# otamatone.net
KiCad netlist of a schematic drawn in EAGLE
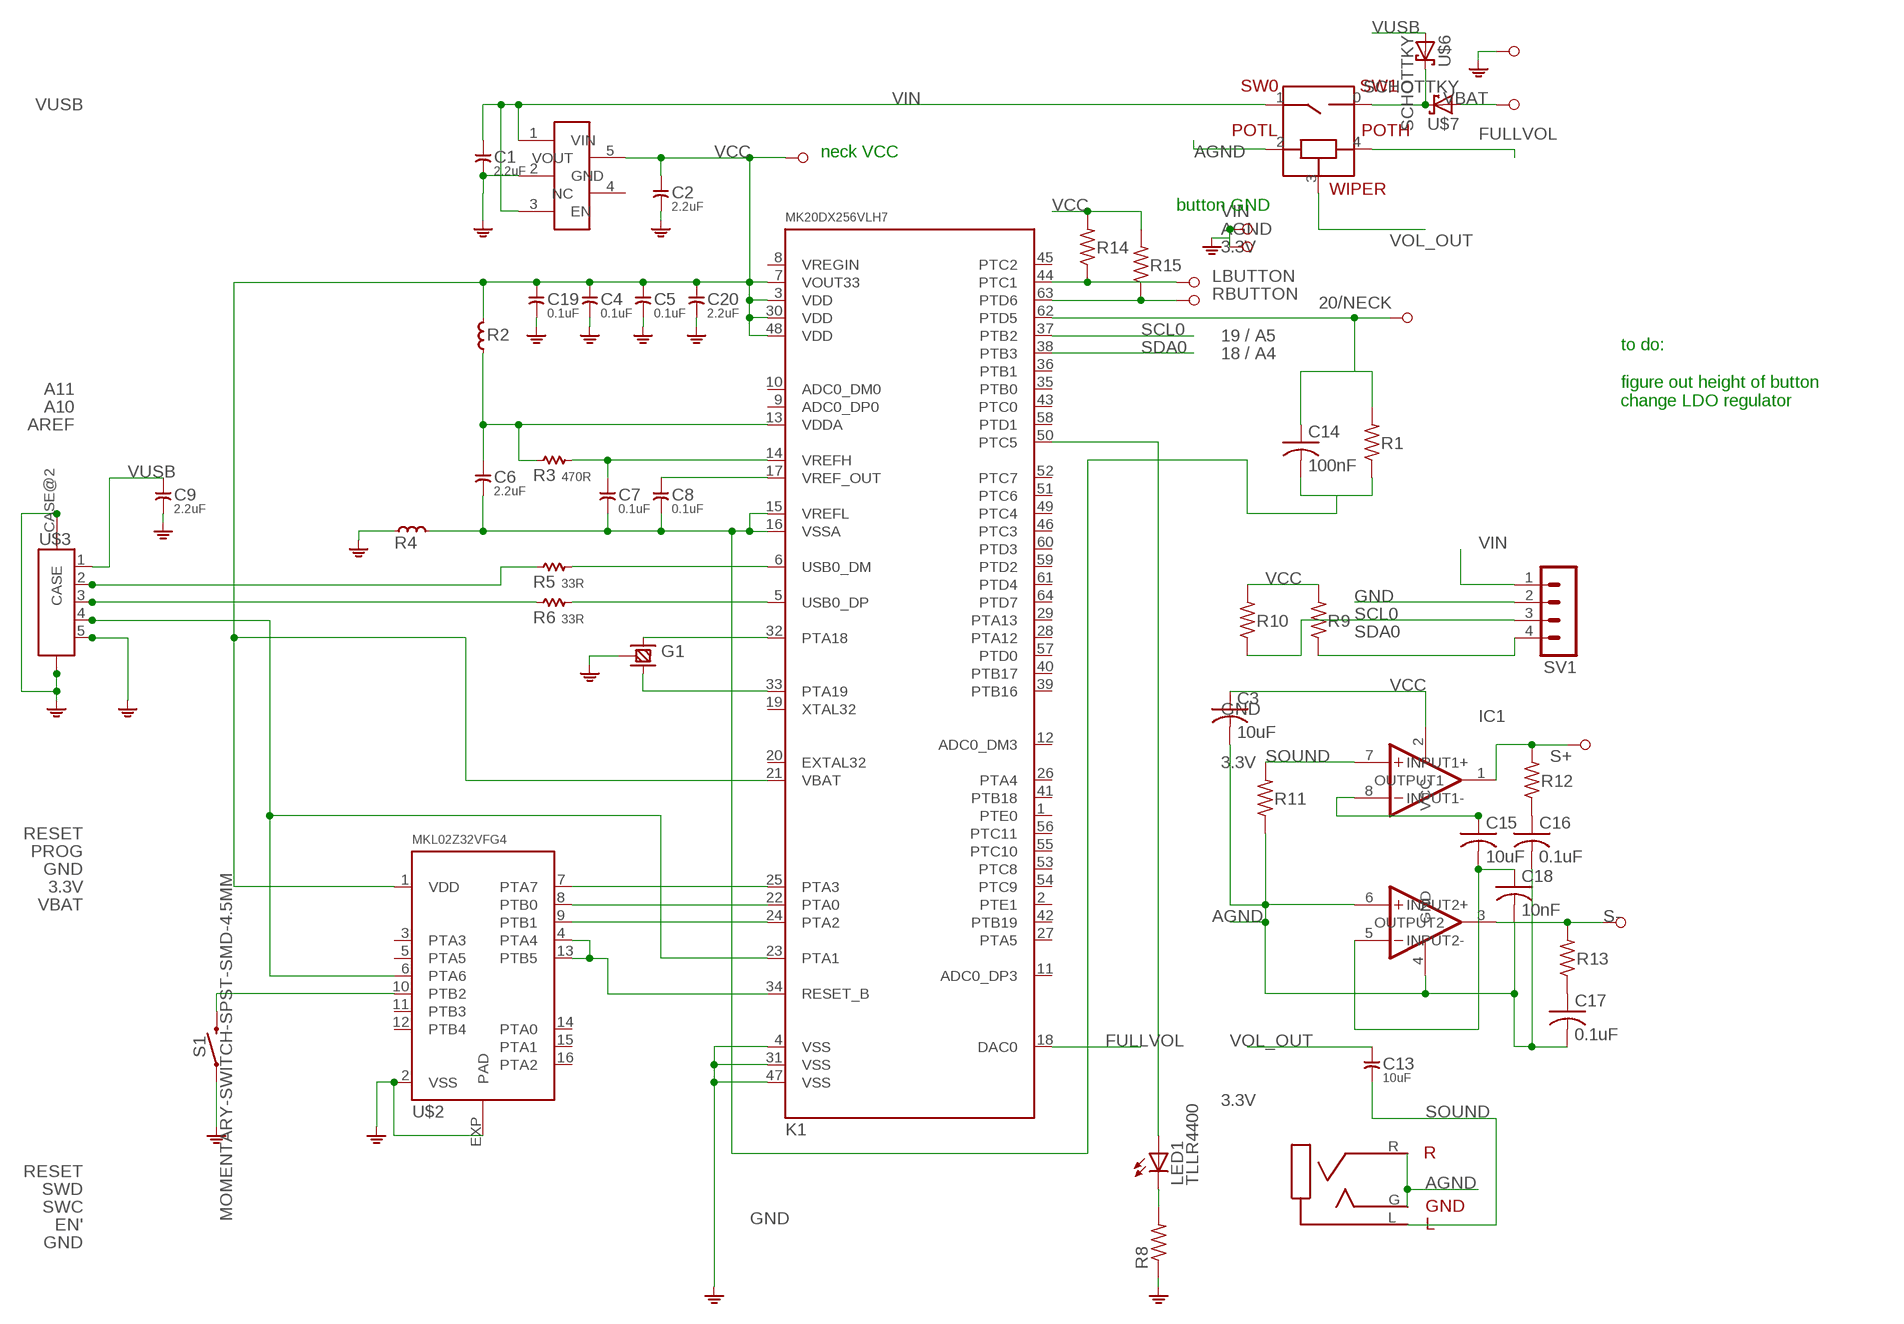
[diagram p0: schematic, sheet 1]

(export (version "E")
  (design (tool "Eeschema 10.0.6"))
  (components
    (comp (ref "B+")
      (value "PIN")
      (footprint "eagle-import:PTH_39MIL")
      (libsource (lib "eagle-import") (part "t32_ref_PIN"))
    )
    (comp (ref "B-")
      (value "PIN")
      (footprint "eagle-import:PTH_39MIL")
      (libsource (lib "eagle-import") (part "t32_ref_PIN"))
    )
    (comp (ref "C1")
      (value "2.2uF")
      (footprint "eagle-import:C0603")
      (libsource (lib "eagle-import") (part "CAPACITOR-2.2UF"))
    )
    (comp (ref "C2")
      (value "2.2uF")
      (footprint "eagle-import:C0603")
      (libsource (lib "eagle-import") (part "CAPACITOR-2.2UF"))
    )
    (comp (ref "C3")
      (value "10uF")
      (footprint "eagle-import:C0603")
      (libsource (lib "eagle-import") (part "C-USC0603"))
    )
    (comp (ref "C4")
      (value "0.1uF")
      (footprint "eagle-import:C0402")
      (libsource (lib "eagle-import") (part "CAPACITOR-0.1UF"))
    )
    (comp (ref "C5")
      (value "0.1uF")
      (footprint "eagle-import:C0402")
      (libsource (lib "eagle-import") (part "CAPACITOR-0.1UF"))
    )
    (comp (ref "C6")
      (value "2.2uF")
      (footprint "eagle-import:C0603")
      (libsource (lib "eagle-import") (part "CAPACITOR-2.2UF"))
    )
    (comp (ref "C7")
      (value "0.1uF")
      (footprint "eagle-import:C0402")
      (libsource (lib "eagle-import") (part "CAPACITOR-0.1UF"))
    )
    (comp (ref "C8")
      (value "0.1uF")
      (footprint "eagle-import:C0402")
      (libsource (lib "eagle-import") (part "CAPACITOR-0.1UF"))
    )
    (comp (ref "C9")
      (value "2.2uF")
      (footprint "eagle-import:C0603")
      (libsource (lib "eagle-import") (part "CAPACITOR-2.2UF"))
    )
    (comp (ref "C13")
      (value "10uF")
      (footprint "eagle-import:C0603")
      (fields (field (name "MF") "Vishay / Vitramon") (field (name "MPN") "VJ0603A220JXACW1BC"))
      (libsource (lib "eagle-import") (part "CAPACITOR-22PF"))
    )
    (comp (ref "C14")
      (value "100nF")
      (footprint "eagle-import:C0402")
      (libsource (lib "eagle-import") (part "C-USC0402"))
    )
    (comp (ref "C15")
      (value "10uF")
      (footprint "eagle-import:C0603")
      (libsource (lib "eagle-import") (part "C-USC0603"))
    )
    (comp (ref "C16")
      (value "0.1uF")
      (footprint "eagle-import:C0603")
      (libsource (lib "eagle-import") (part "C-USC0603"))
    )
    (comp (ref "C17")
      (value "0.1uF")
      (footprint "eagle-import:C0603")
      (libsource (lib "eagle-import") (part "C-USC0603"))
    )
    (comp (ref "C18")
      (value "10nF")
      (footprint "eagle-import:C0603")
      (libsource (lib "eagle-import") (part "C-USC0603"))
    )
    (comp (ref "C19")
      (value "0.1uF")
      (footprint "eagle-import:C0402")
      (libsource (lib "eagle-import") (part "CAPACITOR-0.1UF"))
    )
    (comp (ref "C20")
      (value "2.2uF")
      (footprint "eagle-import:C0603")
      (libsource (lib "eagle-import") (part "CAPACITOR-2.2UF"))
    )
    (comp (ref "G1")
      (value "CRYSTAL-")
      (footprint "eagle-import:CRYS")
      (libsource (lib "eagle-import") (part "CRYSTAL-"))
    )
    (comp (ref "IC1")
      (value "TDA2822MSOP8")
      (footprint "eagle-import:SOP8")
      (libsource (lib "eagle-import") (part "TDA2822MSOP8"))
    )
    (comp (ref "K1")
      (value "MK20DX256VLH7")
      (footprint "eagle-import:LQFP64-05")
      (fields (field (name "MF") "NXP"))
      (libsource (lib "eagle-import") (part "MK20DX256VLH7"))
    )
    (comp (ref "LED1")
      (value "TLLR4400")
      (footprint "eagle-import:LED3MM")
      (fields (field (name "MF") "VISHAY SEMICONDUCTOR"))
      (libsource (lib "eagle-import") (part "TLLR4400"))
    )
    (comp (ref "R1")
      (value "62K")
      (footprint "eagle-import:R0402")
      (libsource (lib "eagle-import") (part "R-US_R0402"))
    )
    (comp (ref "R2")
      (value "FERRITE")
      (footprint "eagle-import:L0603")
      (fields (field (name "MF") "Murata Electronics") (field (name "MPN") " BLM18AG601SN1D"))
      (libsource (lib "eagle-import") (part "FERRITE"))
    )
    (comp (ref "R3")
      (value "470R")
      (footprint "eagle-import:R0402")
      (libsource (lib "eagle-import") (part "RESISTOR-470R"))
    )
    (comp (ref "R4")
      (value "FERRITE")
      (footprint "eagle-import:L0603")
      (fields (field (name "MF") "Murata Electronics") (field (name "MPN") " BLM18AG601SN1D"))
      (libsource (lib "eagle-import") (part "FERRITE"))
    )
    (comp (ref "R5")
      (value "33R")
      (footprint "eagle-import:R0402")
      (libsource (lib "eagle-import") (part "RESISTOR-33R"))
    )
    (comp (ref "R6")
      (value "33R")
      (footprint "eagle-import:R0402")
      (libsource (lib "eagle-import") (part "RESISTOR-33R"))
    )
    (comp (ref "R8")
      (value "R-US_R0603")
      (footprint "eagle-import:R0603")
      (libsource (lib "eagle-import") (part "R-US_R0603"))
    )
    (comp (ref "R9")
      (value "10K")
      (footprint "eagle-import:R0402")
      (libsource (lib "eagle-import") (part "R-US_R0402"))
    )
    (comp (ref "R10")
      (value "10K")
      (footprint "eagle-import:R0402")
      (libsource (lib "eagle-import") (part "R-US_R0402"))
    )
    (comp (ref "R11")
      (value "10K")
      (footprint "eagle-import:R0603")
      (libsource (lib "eagle-import") (part "R-US_R0603"))
    )
    (comp (ref "R12")
      (value "4.7")
      (footprint "eagle-import:R0603")
      (libsource (lib "eagle-import") (part "R-US_R0603"))
    )
    (comp (ref "R13")
      (value "4.7")
      (footprint "eagle-import:R0603")
      (libsource (lib "eagle-import") (part "R-US_R0603"))
    )
    (comp (ref "R14")
      (value "10K")
      (footprint "eagle-import:R0402")
      (libsource (lib "eagle-import") (part "R-US_R0402"))
    )
    (comp (ref "R15")
      (value "10K")
      (footprint "eagle-import:R0402")
      (libsource (lib "eagle-import") (part "R-US_R0402"))
    )
    (comp (ref "S+")
      (value "PINSMT")
      (footprint "eagle-import:SMD")
      (libsource (lib "eagle-import") (part "PINSMT"))
    )
    (comp (ref "S-")
      (value "PINSMT")
      (footprint "eagle-import:SMD")
      (libsource (lib "eagle-import") (part "PINSMT"))
    )
    (comp (ref "S1")
      (value "MOMENTARY-SWITCH-SPST-SMD-4.5MM")
      (footprint "eagle-import:TACTILE_SWITCH_SMD_4.5MM")
      (libsource (lib "eagle-import") (part "MOMENTARY-SWITCH-SPST-SMD-4.5MM"))
    )
    (comp (ref "SV1")
      (value "MA04-1")
      (footprint "eagle-import:MA04-1")
      (libsource (lib "eagle-import") (part "MA04-1"))
    )
    (comp (ref "SX1")
      (value "PIN")
      (footprint "eagle-import:PTH_39MIL")
      (libsource (lib "eagle-import") (part "PIN"))
    )
    (comp (ref "SX2")
      (value "PIN")
      (footprint "eagle-import:PTH_39MIL")
      (libsource (lib "eagle-import") (part "PIN"))
    )
    (comp (ref "SX3")
      (value "PIN")
      (footprint "eagle-import:PTH_39MIL")
      (libsource (lib "eagle-import") (part "PIN"))
    )
    (comp (ref "SX4")
      (value "PIN")
      (footprint "eagle-import:PTH_39MIL")
      (libsource (lib "eagle-import") (part "PIN"))
    )
    (comp (ref "U$1")
      (value "P170S")
      (footprint "eagle-import:5PIN_POT")
      (libsource (lib "eagle-import") (part "P170S"))
    )
    (comp (ref "U$2")
      (value "MKL02Z32VFG4")
      (footprint "eagle-import:QFN16")
      (libsource (lib "eagle-import") (part "MKL02Z32VFG4"))
    )
    (comp (ref "U$3")
      (value "VERT_USB")
      (footprint "eagle-import:TALL_BOI")
      (libsource (lib "eagle-import") (part "VERT_USB"))
    )
    (comp (ref "U$4")
      (value "VERT_JACK")
      (footprint "eagle-import:AUDIOJACK")
      (libsource (lib "eagle-import") (part "VERT_JACK"))
    )
    (comp (ref "U$5")
      (value "AP2112K")
      (footprint "eagle-import:SOT25")
      (libsource (lib "eagle-import") (part "AP2112K"))
    )
    (comp (ref "U$6")
      (value "SCHOTTKY")
      (footprint "eagle-import:LED-0805")
      (libsource (lib "eagle-import") (part "SCHOTTKY"))
    )
    (comp (ref "U$7")
      (value "SCHOTTKY")
      (footprint "eagle-import:LED-0805")
      (libsource (lib "eagle-import") (part "SCHOTTKY"))
    )
    (comp (ref "Z+")
      (value "PINSMT")
      (footprint "eagle-import:SMD")
      (libsource (lib "eagle-import") (part "PINSMT"))
    )
    (comp (ref "Z-")
      (value "PINSMT")
      (footprint "eagle-import:SMD")
      (libsource (lib "eagle-import") (part "PINSMT"))
    )
  )
  (nets
    (net (code "1") (name "/20{slash}NECK") (class "Default")
      (node (ref "C14") (pin "1") (pinfunction "1_1") (pintype "passive"))
      (node (ref "K1") (pin "62") (pinfunction "PTD5_62") (pintype "bidirectional"))
      (node (ref "R1") (pin "2") (pinfunction "2_2") (pintype "passive"))
      (node (ref "Z-") (pin "P$1") (pinfunction "P$1_P$1") (pintype "bidirectional"))
    )
    (net (code "2") (name "/AGND") (class "Default")
      (node (ref "C14") (pin "2") (pinfunction "2_2") (pintype "passive"))
      (node (ref "C16") (pin "2") (pinfunction "2_2") (pintype "passive"))
      (node (ref "C17") (pin "2") (pinfunction "2_2") (pintype "passive"))
      (node (ref "C18") (pin "2") (pinfunction "2_2") (pintype "passive"))
      (node (ref "C3") (pin "2") (pinfunction "2_2") (pintype "passive"))
      (node (ref "C6") (pin "2") (pinfunction "2_2") (pintype "passive"))
      (node (ref "C7") (pin "2") (pinfunction "2_2") (pintype "passive"))
      (node (ref "C8") (pin "2") (pinfunction "2_2") (pintype "passive"))
      (node (ref "IC1") (pin "4") (pinfunction "GND_4") (pintype "bidirectional"))
      (node (ref "IC1") (pin "6") (pinfunction "INPUT2+_6") (pintype "bidirectional"))
      (node (ref "K1") (pin "15") (pinfunction "VREFL_15") (pintype "bidirectional"))
      (node (ref "K1") (pin "16") (pinfunction "VSSA_16") (pintype "bidirectional"))
      (node (ref "R1") (pin "1") (pinfunction "1_1") (pintype "passive"))
      (node (ref "R11") (pin "1") (pinfunction "1_1") (pintype "passive"))
      (node (ref "R4") (pin "2") (pinfunction "2_2") (pintype "passive"))
      (node (ref "U$1") (pin "2") (pinfunction "POTL_2") (pintype "bidirectional"))
      (node (ref "U$4") (pin "G") (pinfunction "GND_G") (pintype "bidirectional"))
      (node (ref "U$4") (pin "R") (pinfunction "R_R") (pintype "bidirectional"))
    )
    (net (code "3") (name "/FULLVOL") (class "Default")
      (node (ref "K1") (pin "18") (pinfunction "DAC0_18") (pintype "bidirectional"))
      (node (ref "U$1") (pin "4") (pinfunction "POTH_4") (pintype "bidirectional"))
    )
    (net (code "4") (name "/LBUTTON") (class "Default")
      (node (ref "K1") (pin "44") (pinfunction "PTC1_44") (pintype "bidirectional"))
      (node (ref "R14") (pin "1") (pinfunction "1_1") (pintype "passive"))
      (node (ref "SX2") (pin "1") (pinfunction "P$1_1") (pintype "bidirectional"))
    )
    (net (code "5") (name "/RBUTTON") (class "Default")
      (node (ref "K1") (pin "63") (pinfunction "PTD6_63") (pintype "bidirectional"))
      (node (ref "R15") (pin "1") (pinfunction "1_1") (pintype "passive"))
      (node (ref "SX4") (pin "1") (pinfunction "P$1_1") (pintype "bidirectional"))
    )
    (net (code "6") (name "/S+") (class "Default")
      (node (ref "IC1") (pin "1") (pinfunction "OUTPUT1_1") (pintype "bidirectional"))
      (node (ref "R12") (pin "2") (pinfunction "2_2") (pintype "passive"))
      (node (ref "S+") (pin "P$1") (pinfunction "P$1_P$1") (pintype "bidirectional"))
    )
    (net (code "7") (name "/S-") (class "Default")
      (node (ref "IC1") (pin "3") (pinfunction "OUTPUT2_3") (pintype "bidirectional"))
      (node (ref "R13") (pin "2") (pinfunction "2_2") (pintype "passive"))
      (node (ref "S-") (pin "P$1") (pinfunction "P$1_P$1") (pintype "bidirectional"))
    )
    (net (code "8") (name "/SCL0") (class "Default")
      (node (ref "K1") (pin "37") (pinfunction "PTB2_37") (pintype "bidirectional"))
      (node (ref "R10") (pin "1") (pinfunction "1_1") (pintype "passive"))
      (node (ref "SV1") (pin "3") (pinfunction "3_3") (pintype "passive"))
    )
    (net (code "9") (name "/SDA0") (class "Default")
      (node (ref "K1") (pin "38") (pinfunction "PTB3_38") (pintype "bidirectional"))
      (node (ref "R9") (pin "1") (pinfunction "1_1") (pintype "passive"))
      (node (ref "SV1") (pin "4") (pinfunction "4_4") (pintype "passive"))
    )
    (net (code "10") (name "/SOUND") (class "Default")
      (node (ref "C13") (pin "2") (pinfunction "2_2") (pintype "passive"))
      (node (ref "IC1") (pin "7") (pinfunction "INPUT1+_7") (pintype "bidirectional"))
      (node (ref "R11") (pin "2") (pinfunction "2_2") (pintype "passive"))
      (node (ref "U$4") (pin "L") (pinfunction "L_L") (pintype "bidirectional"))
    )
    (net (code "11") (name "/VBAT") (class "Default")
      (node (ref "B+") (pin "1") (pinfunction "P$1_1") (pintype "bidirectional"))
      (node (ref "U$7") (pin "+") (pinfunction "A_+") (pintype "passive"))
    )
    (net (code "12") (name "/VCC") (class "Default")
      (node (ref "C19") (pin "1") (pinfunction "1_1") (pintype "passive"))
      (node (ref "C2") (pin "1") (pinfunction "1_1") (pintype "passive"))
      (node (ref "C20") (pin "1") (pinfunction "1_1") (pintype "passive"))
      (node (ref "C3") (pin "1") (pinfunction "1_1") (pintype "passive"))
      (node (ref "C4") (pin "1") (pinfunction "1_1") (pintype "passive"))
      (node (ref "C5") (pin "1") (pinfunction "1_1") (pintype "passive"))
      (node (ref "IC1") (pin "2") (pinfunction "VCC_2") (pintype "bidirectional"))
      (node (ref "K1") (pin "21") (pinfunction "VBAT_21") (pintype "bidirectional"))
      (node (ref "K1") (pin "3") (pinfunction "VDD_3") (pintype "bidirectional"))
      (node (ref "K1") (pin "30") (pinfunction "VDD_30") (pintype "bidirectional"))
      (node (ref "K1") (pin "48") (pinfunction "VDD_48") (pintype "bidirectional"))
      (node (ref "K1") (pin "7") (pinfunction "VOUT33_7") (pintype "bidirectional"))
      (node (ref "R10") (pin "2") (pinfunction "2_2") (pintype "passive"))
      (node (ref "R14") (pin "2") (pinfunction "2_2") (pintype "passive"))
      (node (ref "R15") (pin "2") (pinfunction "2_2") (pintype "passive"))
      (node (ref "R2") (pin "2") (pinfunction "2_2") (pintype "passive"))
      (node (ref "R9") (pin "2") (pinfunction "2_2") (pintype "passive"))
      (node (ref "U$2") (pin "1") (pinfunction "VDD_1") (pintype "bidirectional"))
      (node (ref "U$5") (pin "5") (pinfunction "VOUT_5") (pintype "bidirectional"))
      (node (ref "Z+") (pin "P$1") (pinfunction "P$1_P$1") (pintype "bidirectional"))
    )
    (net (code "13") (name "/VIN") (class "Default")
      (node (ref "C1") (pin "1") (pinfunction "1_1") (pintype "passive"))
      (node (ref "SV1") (pin "1") (pinfunction "1_1") (pintype "passive"))
      (node (ref "U$1") (pin "1") (pinfunction "SW0_1") (pintype "bidirectional"))
      (node (ref "U$5") (pin "1") (pinfunction "VIN_1") (pintype "bidirectional"))
      (node (ref "U$5") (pin "3") (pinfunction "EN_3") (pintype "bidirectional"))
    )
    (net (code "14") (name "/VOL_OUT") (class "Default")
      (node (ref "C13") (pin "1") (pinfunction "1_1") (pintype "passive"))
      (node (ref "U$1") (pin "3") (pinfunction "WIPER_3") (pintype "bidirectional"))
    )
    (net (code "15") (name "/VUSB") (class "Default")
      (node (ref "C9") (pin "1") (pinfunction "1_1") (pintype "passive"))
      (node (ref "U$3") (pin "1") (pinfunction "1_1") (pintype "input"))
      (node (ref "U$6") (pin "+") (pinfunction "A_+") (pintype "passive"))
    )
    (net (code "16") (name "GND") (class "Default")
      (node (ref "B-") (pin "1") (pinfunction "P$1_1") (pintype "bidirectional"))
      (node (ref "C1") (pin "2") (pinfunction "2_2") (pintype "passive"))
      (node (ref "C19") (pin "2") (pinfunction "2_2") (pintype "passive"))
      (node (ref "C2") (pin "2") (pinfunction "2_2") (pintype "passive"))
      (node (ref "C20") (pin "2") (pinfunction "2_2") (pintype "passive"))
      (node (ref "C4") (pin "2") (pinfunction "2_2") (pintype "passive"))
      (node (ref "C5") (pin "2") (pinfunction "2_2") (pintype "passive"))
      (node (ref "C9") (pin "2") (pinfunction "2_2") (pintype "passive"))
      (node (ref "G1") (pin "P$1") (pinfunction "GND_P$1") (pintype "bidirectional"))
      (node (ref "G1") (pin "P$4") (pinfunction "GND_P$4") (pintype "bidirectional"))
      (node (ref "K1") (pin "31") (pinfunction "VSS_31") (pintype "bidirectional"))
      (node (ref "K1") (pin "4") (pinfunction "VSS_4") (pintype "bidirectional"))
      (node (ref "K1") (pin "47") (pinfunction "VSS_47") (pintype "bidirectional"))
      (node (ref "R4") (pin "1") (pinfunction "1_1") (pintype "passive"))
      (node (ref "R8") (pin "1") (pinfunction "1_1") (pintype "passive"))
      (node (ref "S1") (pin "2") (pinfunction "1_2") (pintype "passive"))
      (node (ref "S1") (pin "3") (pinfunction "1_3") (pintype "passive"))
      (node (ref "SV1") (pin "2") (pinfunction "2_2") (pintype "passive"))
      (node (ref "SX1") (pin "1") (pinfunction "P$1_1") (pintype "bidirectional"))
      (node (ref "SX3") (pin "1") (pinfunction "P$1_1") (pintype "bidirectional"))
      (node (ref "U$2") (pin "2") (pinfunction "VSS_2") (pintype "bidirectional"))
      (node (ref "U$2") (pin "EXP") (pinfunction "PAD_EXP") (pintype "bidirectional"))
      (node (ref "U$3") (pin "5") (pinfunction "5_5") (pintype "input"))
      (node (ref "U$3") (pin "CASE") (pinfunction "CASE_CASE") (pintype "input"))
      (node (ref "U$3") (pin "CASE@2") (pinfunction "CASE_CASE@2") (pintype "bidirectional"))
      (node (ref "U$5") (pin "2") (pinfunction "GND_2") (pintype "bidirectional"))
    )
    (net (code "17") (name "Net-(C16-Pad1)") (class "Default")
      (node (ref "C16") (pin "1") (pinfunction "1_1") (pintype "passive"))
      (node (ref "R12") (pin "1") (pinfunction "1_1") (pintype "passive"))
    )
    (net (code "18") (name "Net-(C17-Pad1)") (class "Default")
      (node (ref "C17") (pin "1") (pinfunction "1_1") (pintype "passive"))
      (node (ref "R13") (pin "1") (pinfunction "1_1") (pintype "passive"))
    )
    (net (code "19") (name "Net-(G1-1)") (class "Default")
      (node (ref "G1") (pin "P$2") (pinfunction "1_P$2") (pintype "passive"))
      (node (ref "K1") (pin "32") (pinfunction "PTA18_32") (pintype "bidirectional"))
    )
    (net (code "20") (name "Net-(G1-2)") (class "Default")
      (node (ref "G1") (pin "P$3") (pinfunction "2_P$3") (pintype "passive"))
      (node (ref "K1") (pin "33") (pinfunction "PTA19_33") (pintype "bidirectional"))
    )
    (net (code "21") (name "Net-(IC1-INPUT1-)") (class "Default")
      (node (ref "C15") (pin "1") (pinfunction "1_1") (pintype "passive"))
      (node (ref "IC1") (pin "8") (pinfunction "INPUT1-_8") (pintype "bidirectional"))
    )
    (net (code "22") (name "Net-(IC1-INPUT2-)") (class "Default")
      (node (ref "C15") (pin "2") (pinfunction "2_2") (pintype "passive"))
      (node (ref "C18") (pin "1") (pinfunction "1_1") (pintype "passive"))
      (node (ref "IC1") (pin "5") (pinfunction "INPUT2-_5") (pintype "bidirectional"))
    )
    (net (code "23") (name "Net-(K1-PTA0)") (class "Default")
      (node (ref "K1") (pin "22") (pinfunction "PTA0_22") (pintype "bidirectional"))
      (node (ref "U$2") (pin "8") (pinfunction "PTB0_8") (pintype "bidirectional"))
    )
    (net (code "24") (name "Net-(K1-PTA1)") (class "Default")
      (node (ref "K1") (pin "23") (pinfunction "PTA1_23") (pintype "bidirectional"))
      (node (ref "U$2") (pin "6") (pinfunction "PTA6_6") (pintype "bidirectional"))
      (node (ref "U$3") (pin "4") (pinfunction "4_4") (pintype "input"))
    )
    (net (code "25") (name "Net-(K1-PTA2)") (class "Default")
      (node (ref "K1") (pin "24") (pinfunction "PTA2_24") (pintype "bidirectional"))
      (node (ref "U$2") (pin "9") (pinfunction "PTB1_9") (pintype "bidirectional"))
    )
    (net (code "26") (name "Net-(K1-PTA3)") (class "Default")
      (node (ref "K1") (pin "25") (pinfunction "PTA3_25") (pintype "bidirectional"))
      (node (ref "U$2") (pin "7") (pinfunction "PTA7_7") (pintype "bidirectional"))
    )
    (net (code "27") (name "Net-(K1-PTC5)") (class "Default")
      (node (ref "K1") (pin "50") (pinfunction "PTC5_50") (pintype "bidirectional"))
      (node (ref "LED1") (pin "A") (pinfunction "A_A") (pintype "passive"))
    )
    (net (code "28") (name "Net-(K1-RESET_B)") (class "Default")
      (node (ref "K1") (pin "34") (pinfunction "RESET_B_34") (pintype "bidirectional"))
      (node (ref "U$2") (pin "13") (pinfunction "PTB5_13") (pintype "bidirectional"))
      (node (ref "U$2") (pin "4") (pinfunction "PTA4_4") (pintype "bidirectional"))
    )
    (net (code "29") (name "Net-(K1-USB0_DM)") (class "Default")
      (node (ref "K1") (pin "6") (pinfunction "USB0_DM_6") (pintype "bidirectional"))
      (node (ref "R5") (pin "2") (pinfunction "2_2") (pintype "passive"))
    )
    (net (code "30") (name "Net-(K1-USB0_DP)") (class "Default")
      (node (ref "K1") (pin "5") (pinfunction "USB0_DP_5") (pintype "bidirectional"))
      (node (ref "R6") (pin "2") (pinfunction "2_2") (pintype "passive"))
    )
    (net (code "31") (name "Net-(K1-VDDA)") (class "Default")
      (node (ref "C6") (pin "1") (pinfunction "1_1") (pintype "passive"))
      (node (ref "K1") (pin "13") (pinfunction "VDDA_13") (pintype "bidirectional"))
      (node (ref "R2") (pin "1") (pinfunction "1_1") (pintype "passive"))
      (node (ref "R3") (pin "1") (pinfunction "1_1") (pintype "passive"))
    )
    (net (code "32") (name "Net-(K1-VREFH)") (class "Default")
      (node (ref "C7") (pin "1") (pinfunction "1_1") (pintype "passive"))
      (node (ref "K1") (pin "14") (pinfunction "VREFH_14") (pintype "bidirectional"))
      (node (ref "R3") (pin "2") (pinfunction "2_2") (pintype "passive"))
    )
    (net (code "33") (name "Net-(K1-VREF_OUT)") (class "Default")
      (node (ref "C8") (pin "1") (pinfunction "1_1") (pintype "passive"))
      (node (ref "K1") (pin "17") (pinfunction "VREF_OUT_17") (pintype "bidirectional"))
    )
    (net (code "34") (name "Net-(LED1-C)") (class "Default")
      (node (ref "LED1") (pin "K") (pinfunction "C_K") (pintype "passive"))
      (node (ref "R8") (pin "2") (pinfunction "2_2") (pintype "passive"))
    )
    (net (code "35") (name "Net-(R5-Pad1)") (class "Default")
      (node (ref "R5") (pin "1") (pinfunction "1_1") (pintype "passive"))
      (node (ref "U$3") (pin "2") (pinfunction "2_2") (pintype "input"))
    )
    (net (code "36") (name "Net-(R6-Pad1)") (class "Default")
      (node (ref "R6") (pin "1") (pinfunction "1_1") (pintype "passive"))
      (node (ref "U$3") (pin "3") (pinfunction "3_3") (pintype "input"))
    )
    (net (code "37") (name "Net-(U$1-SW1)") (class "Default")
      (node (ref "U$1") (pin "0") (pinfunction "SW1_0") (pintype "bidirectional"))
      (node (ref "U$6") (pin "-") (pinfunction "C_-") (pintype "passive"))
      (node (ref "U$7") (pin "-") (pinfunction "C_-") (pintype "passive"))
    )
    (net (code "38") (name "Net-(U$2-PTB2)") (class "Default")
      (node (ref "S1") (pin "1") (pinfunction "2_1") (pintype "passive"))
      (node (ref "S1") (pin "4") (pinfunction "2_4") (pintype "passive"))
      (node (ref "U$2") (pin "10") (pinfunction "PTB2_10") (pintype "bidirectional"))
    )
    (net (code "39") (name "unconnected-(K1-ADC0_DM0-Pad10)") (class "Default")
      (node (ref "K1") (pin "10") (pinfunction "ADC0_DM0_10") (pintype "bidirectional"))
    )
    (net (code "40") (name "unconnected-(K1-ADC0_DM3-Pad12)") (class "Default")
      (node (ref "K1") (pin "12") (pinfunction "ADC0_DM3_12") (pintype "bidirectional"))
    )
    (net (code "41") (name "unconnected-(K1-ADC0_DP0-Pad9)") (class "Default")
      (node (ref "K1") (pin "9") (pinfunction "ADC0_DP0_9") (pintype "bidirectional"))
    )
    (net (code "42") (name "unconnected-(K1-ADC0_DP3-Pad11)") (class "Default")
      (node (ref "K1") (pin "11") (pinfunction "ADC0_DP3_11") (pintype "bidirectional"))
    )
    (net (code "43") (name "unconnected-(K1-EXTAL32-Pad20)") (class "Default")
      (node (ref "K1") (pin "20") (pinfunction "EXTAL32_20") (pintype "bidirectional"))
    )
    (net (code "44") (name "unconnected-(K1-PTA4-Pad26)") (class "Default")
      (node (ref "K1") (pin "26") (pinfunction "PTA4_26") (pintype "bidirectional"))
    )
    (net (code "45") (name "unconnected-(K1-PTA5-Pad27)") (class "Default")
      (node (ref "K1") (pin "27") (pinfunction "PTA5_27") (pintype "bidirectional"))
    )
    (net (code "46") (name "unconnected-(K1-PTA12-Pad28)") (class "Default")
      (node (ref "K1") (pin "28") (pinfunction "PTA12_28") (pintype "bidirectional"))
    )
    (net (code "47") (name "unconnected-(K1-PTA13-Pad29)") (class "Default")
      (node (ref "K1") (pin "29") (pinfunction "PTA13_29") (pintype "bidirectional"))
    )
    (net (code "48") (name "unconnected-(K1-PTB0-Pad35)") (class "Default")
      (node (ref "K1") (pin "35") (pinfunction "PTB0_35") (pintype "bidirectional"))
    )
    (net (code "49") (name "unconnected-(K1-PTB1-Pad36)") (class "Default")
      (node (ref "K1") (pin "36") (pinfunction "PTB1_36") (pintype "bidirectional"))
    )
    (net (code "50") (name "unconnected-(K1-PTB16-Pad39)") (class "Default")
      (node (ref "K1") (pin "39") (pinfunction "PTB16_39") (pintype "bidirectional"))
    )
    (net (code "51") (name "unconnected-(K1-PTB17-Pad40)") (class "Default")
      (node (ref "K1") (pin "40") (pinfunction "PTB17_40") (pintype "bidirectional"))
    )
    (net (code "52") (name "unconnected-(K1-PTB18-Pad41)") (class "Default")
      (node (ref "K1") (pin "41") (pinfunction "PTB18_41") (pintype "bidirectional"))
    )
    (net (code "53") (name "unconnected-(K1-PTB19-Pad42)") (class "Default")
      (node (ref "K1") (pin "42") (pinfunction "PTB19_42") (pintype "bidirectional"))
    )
    (net (code "54") (name "unconnected-(K1-PTC0-Pad43)") (class "Default")
      (node (ref "K1") (pin "43") (pinfunction "PTC0_43") (pintype "bidirectional"))
    )
    (net (code "55") (name "unconnected-(K1-PTC2-Pad45)") (class "Default")
      (node (ref "K1") (pin "45") (pinfunction "PTC2_45") (pintype "bidirectional"))
    )
    (net (code "56") (name "unconnected-(K1-PTC3-Pad46)") (class "Default")
      (node (ref "K1") (pin "46") (pinfunction "PTC3_46") (pintype "bidirectional"))
    )
    (net (code "57") (name "unconnected-(K1-PTC4-Pad49)") (class "Default")
      (node (ref "K1") (pin "49") (pinfunction "PTC4_49") (pintype "bidirectional"))
    )
    (net (code "58") (name "unconnected-(K1-PTC6-Pad51)") (class "Default")
      (node (ref "K1") (pin "51") (pinfunction "PTC6_51") (pintype "bidirectional"))
    )
    (net (code "59") (name "unconnected-(K1-PTC7-Pad52)") (class "Default")
      (node (ref "K1") (pin "52") (pinfunction "PTC7_52") (pintype "bidirectional"))
    )
    (net (code "60") (name "unconnected-(K1-PTC8-Pad53)") (class "Default")
      (node (ref "K1") (pin "53") (pinfunction "PTC8_53") (pintype "bidirectional"))
    )
    (net (code "61") (name "unconnected-(K1-PTC9-Pad54)") (class "Default")
      (node (ref "K1") (pin "54") (pinfunction "PTC9_54") (pintype "bidirectional"))
    )
    (net (code "62") (name "unconnected-(K1-PTC10-Pad55)") (class "Default")
      (node (ref "K1") (pin "55") (pinfunction "PTC10_55") (pintype "bidirectional"))
    )
    (net (code "63") (name "unconnected-(K1-PTC11-Pad56)") (class "Default")
      (node (ref "K1") (pin "56") (pinfunction "PTC11_56") (pintype "bidirectional"))
    )
    (net (code "64") (name "unconnected-(K1-PTD0-Pad57)") (class "Default")
      (node (ref "K1") (pin "57") (pinfunction "PTD0_57") (pintype "bidirectional"))
    )
    (net (code "65") (name "unconnected-(K1-PTD1-Pad58)") (class "Default")
      (node (ref "K1") (pin "58") (pinfunction "PTD1_58") (pintype "bidirectional"))
    )
    (net (code "66") (name "unconnected-(K1-PTD2-Pad59)") (class "Default")
      (node (ref "K1") (pin "59") (pinfunction "PTD2_59") (pintype "bidirectional"))
    )
    (net (code "67") (name "unconnected-(K1-PTD3-Pad60)") (class "Default")
      (node (ref "K1") (pin "60") (pinfunction "PTD3_60") (pintype "bidirectional"))
    )
    (net (code "68") (name "unconnected-(K1-PTD4-Pad61)") (class "Default")
      (node (ref "K1") (pin "61") (pinfunction "PTD4_61") (pintype "bidirectional"))
    )
    (net (code "69") (name "unconnected-(K1-PTD7-Pad64)") (class "Default")
      (node (ref "K1") (pin "64") (pinfunction "PTD7_64") (pintype "bidirectional"))
    )
    (net (code "70") (name "unconnected-(K1-PTE0-Pad1)") (class "Default")
      (node (ref "K1") (pin "1") (pinfunction "PTE0_1") (pintype "bidirectional"))
    )
    (net (code "71") (name "unconnected-(K1-PTE1-Pad2)") (class "Default")
      (node (ref "K1") (pin "2") (pinfunction "PTE1_2") (pintype "bidirectional"))
    )
    (net (code "72") (name "unconnected-(K1-VREGIN-Pad8)") (class "Default")
      (node (ref "K1") (pin "8") (pinfunction "VREGIN_8") (pintype "bidirectional"))
    )
    (net (code "73") (name "unconnected-(K1-XTAL32-Pad19)") (class "Default")
      (node (ref "K1") (pin "19") (pinfunction "XTAL32_19") (pintype "bidirectional"))
    )
    (net (code "74") (name "unconnected-(U$2-PTA0-Pad14)") (class "Default")
      (node (ref "U$2") (pin "14") (pinfunction "PTA0_14") (pintype "bidirectional"))
    )
    (net (code "75") (name "unconnected-(U$2-PTA1-Pad15)") (class "Default")
      (node (ref "U$2") (pin "15") (pinfunction "PTA1_15") (pintype "bidirectional"))
    )
    (net (code "76") (name "unconnected-(U$2-PTA2-Pad16)") (class "Default")
      (node (ref "U$2") (pin "16") (pinfunction "PTA2_16") (pintype "bidirectional"))
    )
    (net (code "77") (name "unconnected-(U$2-PTA3-Pad3)") (class "Default")
      (node (ref "U$2") (pin "3") (pinfunction "PTA3_3") (pintype "bidirectional"))
    )
    (net (code "78") (name "unconnected-(U$2-PTA5-Pad5)") (class "Default")
      (node (ref "U$2") (pin "5") (pinfunction "PTA5_5") (pintype "bidirectional"))
    )
    (net (code "79") (name "unconnected-(U$2-PTB3-Pad11)") (class "Default")
      (node (ref "U$2") (pin "11") (pinfunction "PTB3_11") (pintype "bidirectional"))
    )
    (net (code "80") (name "unconnected-(U$2-PTB4-Pad12)") (class "Default")
      (node (ref "U$2") (pin "12") (pinfunction "PTB4_12") (pintype "bidirectional"))
    )
    (net (code "81") (name "unconnected-(U$5-NC-Pad4)") (class "Default")
      (node (ref "U$5") (pin "4") (pinfunction "NC_4") (pintype "bidirectional"))
    )
  )
)
